# SCH_Cart_Main_PCB_2023-04-11.net
KiCad netlist of a schematic drawn in EasyEDA
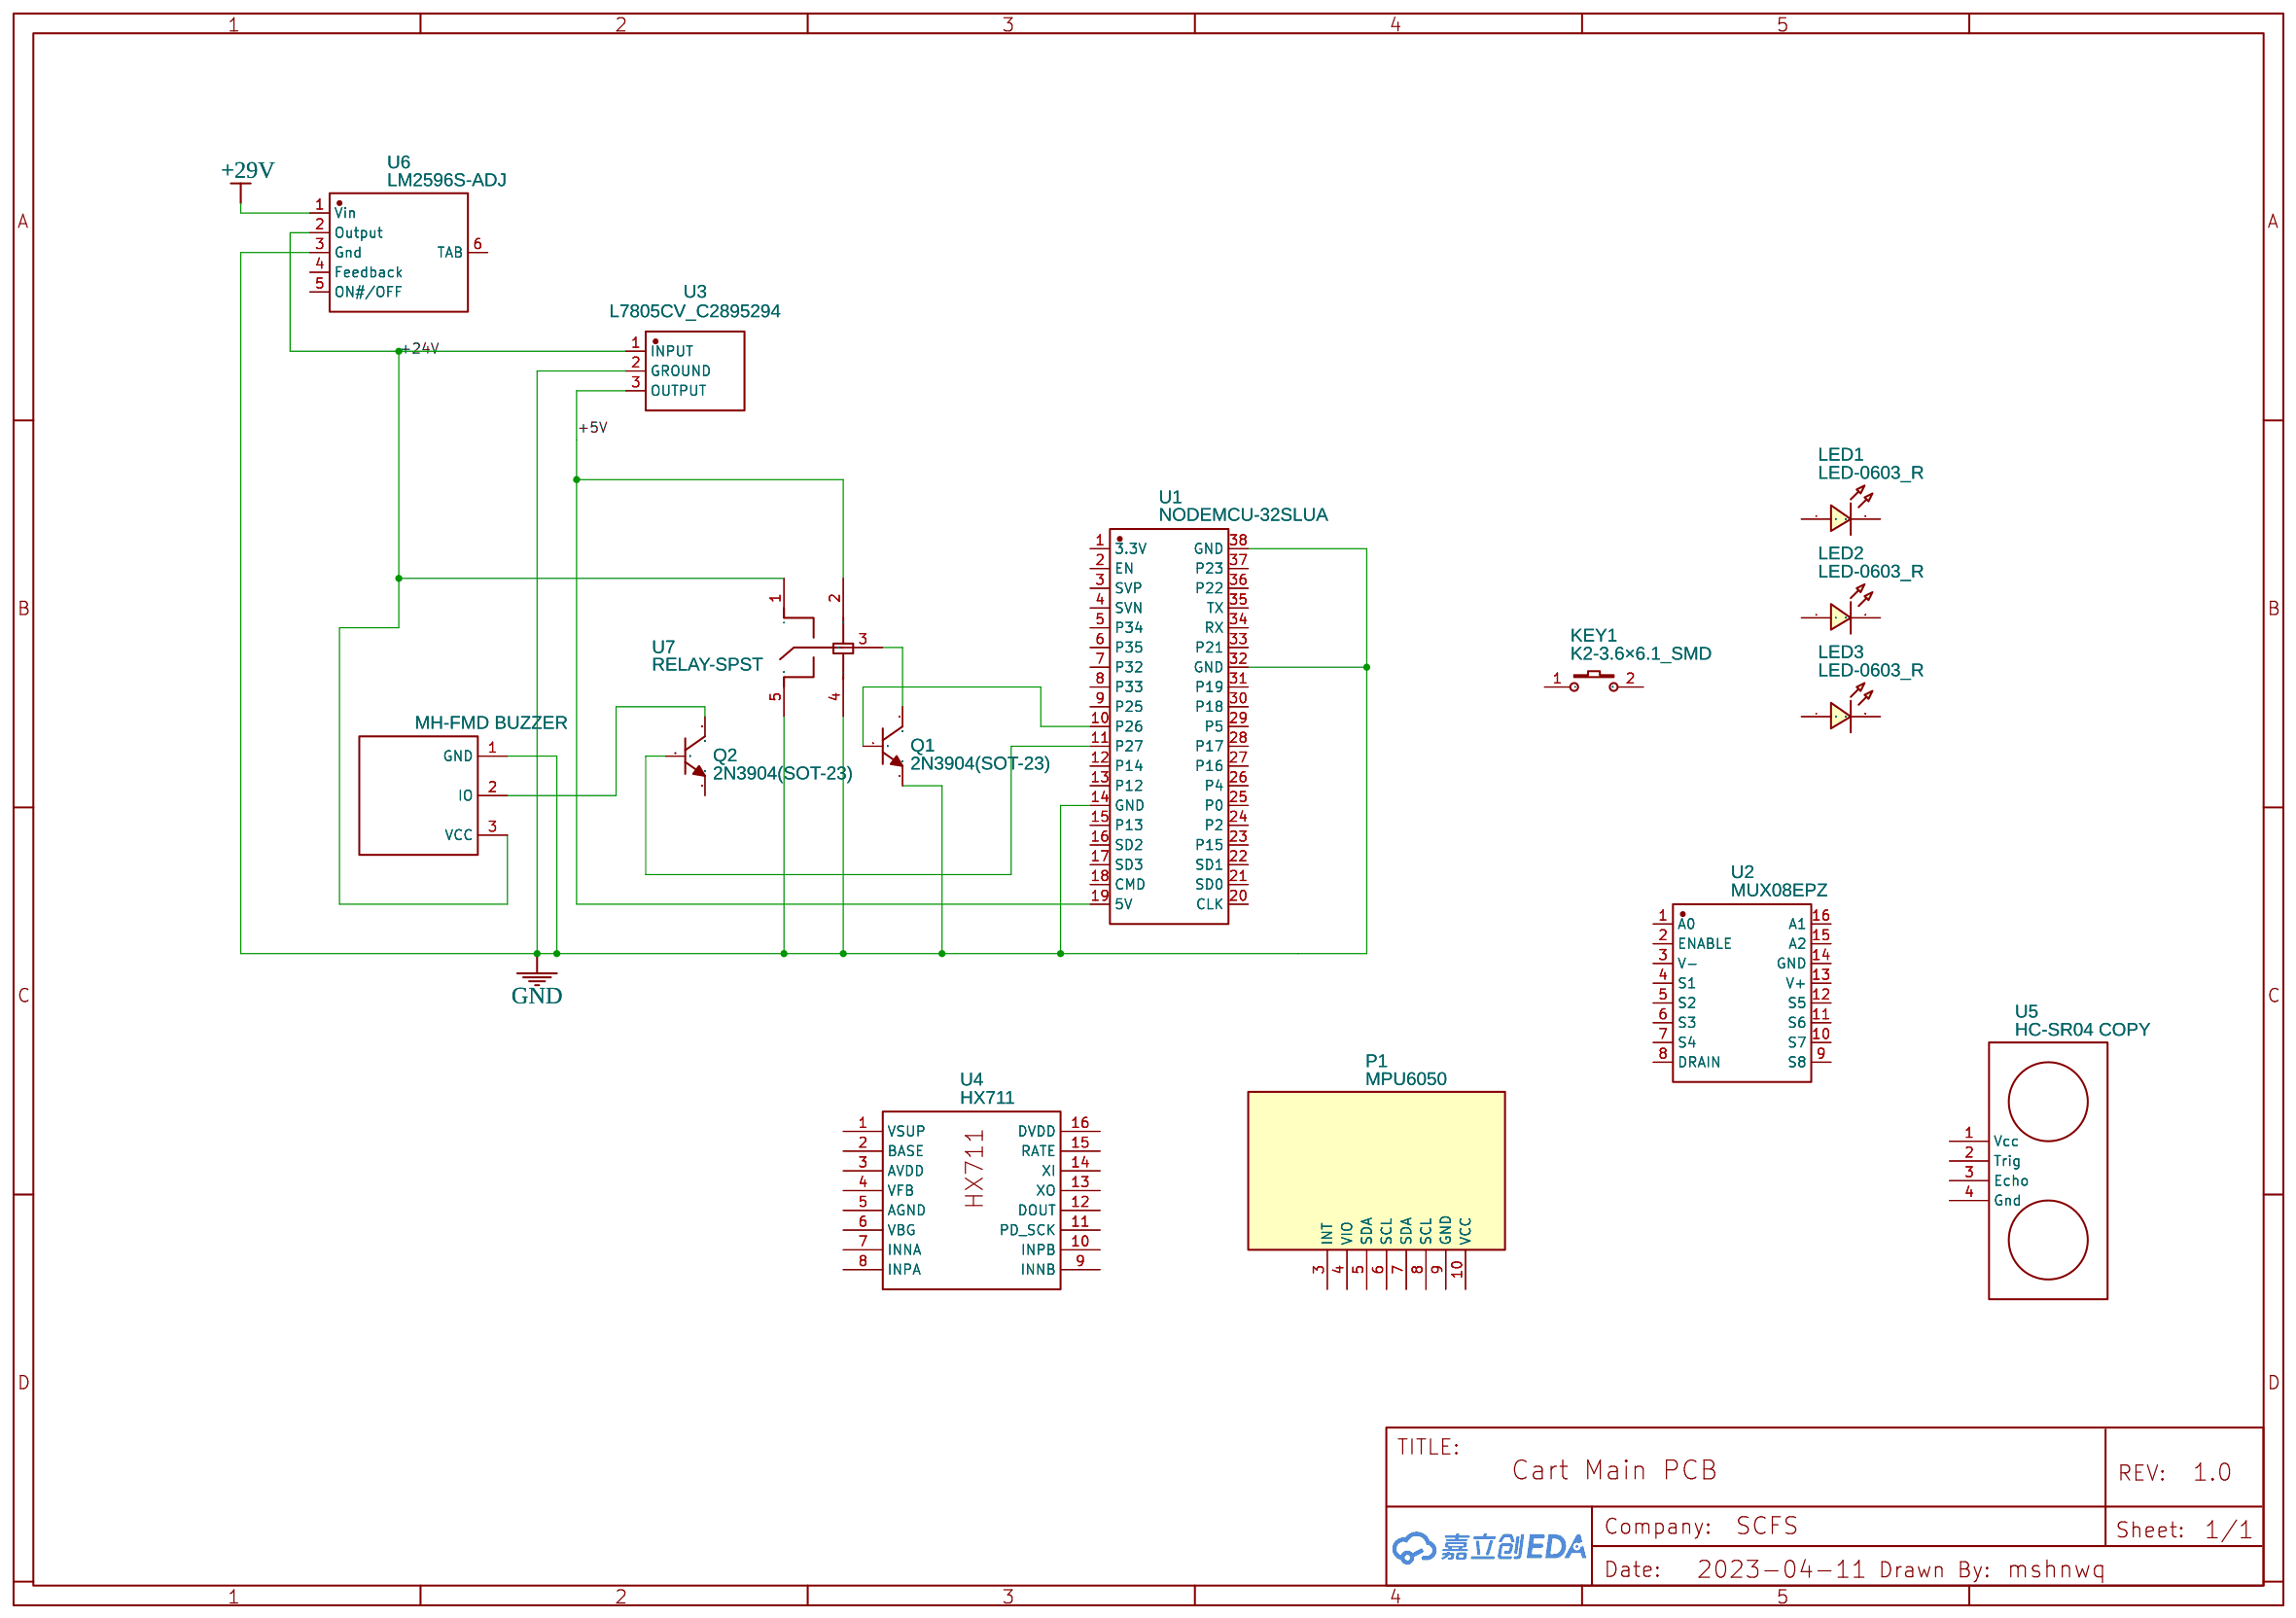
[diagram p0: schematic sheet]

(export (version "E")
  (design (tool "Eeschema 10.0.6"))
  (components
    (comp (ref "GND")
      (value "MH-FMD BUZZER")
      (fields (field (name "BOM_Supplier Part") "MH-FMD"))
      (libsource (lib "") (part "MH-FMD BUZZER"))
    )
    (comp (ref "KEY1")
      (value "K2-3.6×6.1_SMD")
      (fields
        (field (name "BOM_Manufacturer Part") "K2-1107ST-A4SW-06")
        (field (name "BOM_Supplier Part") "C118141")
      )
      (libsource (lib "") (part "K2-3.6×6.1_SMD"))
    )
    (comp (ref "LED1")
      (value "LED-0603_R")
      (fields
        (field (name "BOM_Manufacturer Part") "19-217/R6C-AL1M2VY/3T")
        (field (name "BOM_Supplier Part") "C72044")
      )
      (libsource (lib "") (part "LED-0603_R"))
    )
    (comp (ref "LED2")
      (value "LED-0603_R")
      (fields
        (field (name "BOM_Manufacturer Part") "19-217/R6C-AL1M2VY/3T")
        (field (name "BOM_Supplier Part") "C72044")
      )
      (libsource (lib "") (part "LED-0603_R"))
    )
    (comp (ref "LED3")
      (value "LED-0603_R")
      (fields
        (field (name "BOM_Manufacturer Part") "19-217/R6C-AL1M2VY/3T")
        (field (name "BOM_Supplier Part") "C72044")
      )
      (libsource (lib "") (part "LED-0603_R"))
    )
    (comp (ref "P1") (value "MPU6050") (libsource (lib "") (part "MPU6050")))
    (comp (ref "Q1")
      (value "2N3904(SOT-23)")
      (fields
        (field (name "BOM_Manufacturer Part") "2n3904S-RTK/PS")
        (field (name "BOM_Supplier Part") "C18536")
      )
      (libsource (lib "") (part "2N3904(SOT-23)"))
    )
    (comp (ref "Q2")
      (value "2N3904(SOT-23)")
      (fields
        (field (name "BOM_Manufacturer Part") "2n3904S-RTK/PS")
        (field (name "BOM_Supplier Part") "C18536")
      )
      (libsource (lib "") (part "2N3904(SOT-23)"))
    )
    (comp (ref "U1")
      (value "NODEMCU-32SLUA")
      (fields
        (field (name "BOM_Manufacturer Part") "NodeMCU-32SLua")
        (field (name "BOM_Supplier Part") "C111436")
      )
      (libsource (lib "") (part "NODEMCU-32SLUA"))
    )
    (comp (ref "U2")
      (value "MUX08EPZ")
      (fields (field (name "BOM_Supplier Part") "C690856"))
      (libsource (lib "") (part "MUX08EPZ"))
    )
    (comp (ref "U3")
      (value "L7805CV_C2895294")
      (fields
        (field (name "BOM_Manufacturer Part") "L7805CV带散热器")
        (field (name "BOM_Supplier Part") "C2895294")
      )
      (libsource (lib "") (part "L7805CV_C2895294"))
    )
    (comp (ref "U4")
      (value "HX711")
      (fields (field (name "BOM_Supplier Part") "C43656"))
      (libsource (lib "") (part "HX711"))
    )
    (comp (ref "U5") (value "HC-SR04 COPY") (libsource (lib "") (part "HC-SR04 COPY")))
    (comp (ref "U6")
      (value "LM2596S-ADJ")
      (fields (field (name "BOM_Supplier Part") "C347423"))
      (libsource (lib "") (part "LM2596S-ADJ"))
    )
    (comp (ref "U7")
      (value "RELAY-SPST")
      (fields
        (field (name "BOM_Manufacturer Part") "Relay-SPST")
        (field (name "BOM_Supplier Part") "C2941249")
      )
      (libsource (lib "") (part "RELAY-SPST"))
    )
  )
  (nets
    (net (code "1") (name "+29V") (class "Default")
      (node (ref "U6") (pin "1") (pinfunction "Vin_1") (pintype "unspecified"))
    )
    (net (code "2") (name "/+5V") (class "Default")
      (node (ref "U1") (pin "19") (pinfunction "5V_19") (pintype "unspecified"))
      (node (ref "U3") (pin "3") (pinfunction "OUTPUT_3") (pintype "unspecified"))
      (node (ref "U7") (pin "2") (pinfunction "2_2") (pintype "unspecified"))
    )
    (net (code "3") (name "/+24V") (class "Default")
      (node (ref "GND") (pin "3") (pinfunction "VCC_3") (pintype "unspecified"))
      (node (ref "U3") (pin "1") (pinfunction "INPUT_1") (pintype "unspecified"))
      (node (ref "U6") (pin "2") (pinfunction "Output_2") (pintype "unspecified"))
      (node (ref "U7") (pin "1") (pinfunction "1_1") (pintype "unspecified"))
    )
    (net (code "4") (name "GND") (class "Default")
      (node (ref "GND") (pin "1") (pinfunction "GND_1") (pintype "unspecified"))
      (node (ref "Q1") (pin "1") (pinfunction "E_1") (pintype "input"))
      (node (ref "U1") (pin "14") (pinfunction "GND_14") (pintype "unspecified"))
      (node (ref "U1") (pin "32") (pinfunction "GND_32") (pintype "unspecified"))
      (node (ref "U1") (pin "38") (pinfunction "GND_38") (pintype "unspecified"))
      (node (ref "U3") (pin "2") (pinfunction "GROUND_2") (pintype "unspecified"))
      (node (ref "U6") (pin "3") (pinfunction "Gnd_3") (pintype "unspecified"))
      (node (ref "U7") (pin "4") (pinfunction "4_4") (pintype "unspecified"))
      (node (ref "U7") (pin "5") (pinfunction "5_5") (pintype "unspecified"))
    )
    (net (code "5") (name "Net-(GND-IO)") (class "Default")
      (node (ref "GND") (pin "2") (pinfunction "IO_2") (pintype "unspecified"))
      (node (ref "Q2") (pin "3") (pinfunction "C_3") (pintype "input"))
    )
    (net (code "6") (name "Net-(Q1-B)") (class "Default")
      (node (ref "Q1") (pin "2") (pinfunction "B_2") (pintype "input"))
      (node (ref "U1") (pin "10") (pinfunction "P26_10") (pintype "unspecified"))
    )
    (net (code "7") (name "Net-(Q1-C)") (class "Default")
      (node (ref "Q1") (pin "3") (pinfunction "C_3") (pintype "input"))
      (node (ref "U7") (pin "3") (pinfunction "3_3") (pintype "unspecified"))
    )
    (net (code "8") (name "Net-(Q2-B)") (class "Default")
      (node (ref "Q2") (pin "2") (pinfunction "B_2") (pintype "input"))
      (node (ref "U1") (pin "11") (pinfunction "P27_11") (pintype "unspecified"))
    )
    (net (code "9") (name "unconnected-(KEY1-Pad1)") (class "Default")
      (node (ref "KEY1") (pin "1") (pinfunction "1_1") (pintype "unspecified"))
    )
    (net (code "10") (name "unconnected-(KEY1-Pad2)") (class "Default")
      (node (ref "KEY1") (pin "2") (pinfunction "2_2") (pintype "unspecified"))
    )
    (net (code "11") (name "unconnected-(LED1-Pad1)") (class "Default")
      (node (ref "LED1") (pin "1") (pinfunction "1_1") (pintype "unspecified"))
    )
    (net (code "12") (name "unconnected-(LED1-Pad2)") (class "Default")
      (node (ref "LED1") (pin "2") (pinfunction "2_2") (pintype "unspecified"))
    )
    (net (code "13") (name "unconnected-(LED2-Pad1)") (class "Default")
      (node (ref "LED2") (pin "1") (pinfunction "1_1") (pintype "unspecified"))
    )
    (net (code "14") (name "unconnected-(LED2-Pad2)") (class "Default")
      (node (ref "LED2") (pin "2") (pinfunction "2_2") (pintype "unspecified"))
    )
    (net (code "15") (name "unconnected-(LED3-Pad1)") (class "Default")
      (node (ref "LED3") (pin "1") (pinfunction "1_1") (pintype "unspecified"))
    )
    (net (code "16") (name "unconnected-(LED3-Pad2)") (class "Default")
      (node (ref "LED3") (pin "2") (pinfunction "2_2") (pintype "unspecified"))
    )
    (net (code "17") (name "unconnected-(P1-GND-Pad9)") (class "Default")
      (node (ref "P1") (pin "9") (pinfunction "GND_9") (pintype "unspecified"))
    )
    (net (code "18") (name "unconnected-(P1-INT-Pad3)") (class "Default")
      (node (ref "P1") (pin "3") (pinfunction "INT_3") (pintype "unspecified"))
    )
    (net (code "19") (name "unconnected-(P1-SCL-Pad6)") (class "Default")
      (node (ref "P1") (pin "6") (pinfunction "SCL_6") (pintype "unspecified"))
    )
    (net (code "20") (name "unconnected-(P1-SCL-Pad8)") (class "Default")
      (node (ref "P1") (pin "8") (pinfunction "SCL_8") (pintype "unspecified"))
    )
    (net (code "21") (name "unconnected-(P1-SDA-Pad5)") (class "Default")
      (node (ref "P1") (pin "5") (pinfunction "SDA_5") (pintype "unspecified"))
    )
    (net (code "22") (name "unconnected-(P1-SDA-Pad7)") (class "Default")
      (node (ref "P1") (pin "7") (pinfunction "SDA_7") (pintype "unspecified"))
    )
    (net (code "23") (name "unconnected-(P1-VCC-Pad10)") (class "Default")
      (node (ref "P1") (pin "10") (pinfunction "VCC_10") (pintype "unspecified"))
    )
    (net (code "24") (name "unconnected-(P1-VIO-Pad4)") (class "Default")
      (node (ref "P1") (pin "4") (pinfunction "VIO_4") (pintype "unspecified"))
    )
    (net (code "25") (name "unconnected-(Q2-E-Pad1)") (class "Default")
      (node (ref "Q2") (pin "1") (pinfunction "E_1") (pintype "input"))
    )
    (net (code "26") (name "unconnected-(U1-3.3V-Pad1)") (class "Default")
      (node (ref "U1") (pin "1") (pinfunction "3.3V_1") (pintype "unspecified"))
    )
    (net (code "27") (name "unconnected-(U1-CLK-Pad20)") (class "Default")
      (node (ref "U1") (pin "20") (pinfunction "CLK_20") (pintype "unspecified"))
    )
    (net (code "28") (name "unconnected-(U1-CMD-Pad18)") (class "Default")
      (node (ref "U1") (pin "18") (pinfunction "CMD_18") (pintype "unspecified"))
    )
    (net (code "29") (name "unconnected-(U1-EN-Pad2)") (class "Default")
      (node (ref "U1") (pin "2") (pinfunction "EN_2") (pintype "unspecified"))
    )
    (net (code "30") (name "unconnected-(U1-P0-Pad25)") (class "Default")
      (node (ref "U1") (pin "25") (pinfunction "P0_25") (pintype "unspecified"))
    )
    (net (code "31") (name "unconnected-(U1-P2-Pad24)") (class "Default")
      (node (ref "U1") (pin "24") (pinfunction "P2_24") (pintype "unspecified"))
    )
    (net (code "32") (name "unconnected-(U1-P4-Pad26)") (class "Default")
      (node (ref "U1") (pin "26") (pinfunction "P4_26") (pintype "unspecified"))
    )
    (net (code "33") (name "unconnected-(U1-P5-Pad29)") (class "Default")
      (node (ref "U1") (pin "29") (pinfunction "P5_29") (pintype "unspecified"))
    )
    (net (code "34") (name "unconnected-(U1-P12-Pad13)") (class "Default")
      (node (ref "U1") (pin "13") (pinfunction "P12_13") (pintype "unspecified"))
    )
    (net (code "35") (name "unconnected-(U1-P13-Pad15)") (class "Default")
      (node (ref "U1") (pin "15") (pinfunction "P13_15") (pintype "unspecified"))
    )
    (net (code "36") (name "unconnected-(U1-P14-Pad12)") (class "Default")
      (node (ref "U1") (pin "12") (pinfunction "P14_12") (pintype "unspecified"))
    )
    (net (code "37") (name "unconnected-(U1-P15-Pad23)") (class "Default")
      (node (ref "U1") (pin "23") (pinfunction "P15_23") (pintype "unspecified"))
    )
    (net (code "38") (name "unconnected-(U1-P16-Pad27)") (class "Default")
      (node (ref "U1") (pin "27") (pinfunction "P16_27") (pintype "unspecified"))
    )
    (net (code "39") (name "unconnected-(U1-P17-Pad28)") (class "Default")
      (node (ref "U1") (pin "28") (pinfunction "P17_28") (pintype "unspecified"))
    )
    (net (code "40") (name "unconnected-(U1-P18-Pad30)") (class "Default")
      (node (ref "U1") (pin "30") (pinfunction "P18_30") (pintype "unspecified"))
    )
    (net (code "41") (name "unconnected-(U1-P19-Pad31)") (class "Default")
      (node (ref "U1") (pin "31") (pinfunction "P19_31") (pintype "unspecified"))
    )
    (net (code "42") (name "unconnected-(U1-P21-Pad33)") (class "Default")
      (node (ref "U1") (pin "33") (pinfunction "P21_33") (pintype "unspecified"))
    )
    (net (code "43") (name "unconnected-(U1-P22-Pad36)") (class "Default")
      (node (ref "U1") (pin "36") (pinfunction "P22_36") (pintype "unspecified"))
    )
    (net (code "44") (name "unconnected-(U1-P23-Pad37)") (class "Default")
      (node (ref "U1") (pin "37") (pinfunction "P23_37") (pintype "unspecified"))
    )
    (net (code "45") (name "unconnected-(U1-P25-Pad9)") (class "Default")
      (node (ref "U1") (pin "9") (pinfunction "P25_9") (pintype "unspecified"))
    )
    (net (code "46") (name "unconnected-(U1-P32-Pad7)") (class "Default")
      (node (ref "U1") (pin "7") (pinfunction "P32_7") (pintype "unspecified"))
    )
    (net (code "47") (name "unconnected-(U1-P33-Pad8)") (class "Default")
      (node (ref "U1") (pin "8") (pinfunction "P33_8") (pintype "unspecified"))
    )
    (net (code "48") (name "unconnected-(U1-P34-Pad5)") (class "Default")
      (node (ref "U1") (pin "5") (pinfunction "P34_5") (pintype "unspecified"))
    )
    (net (code "49") (name "unconnected-(U1-P35-Pad6)") (class "Default")
      (node (ref "U1") (pin "6") (pinfunction "P35_6") (pintype "unspecified"))
    )
    (net (code "50") (name "unconnected-(U1-RX-Pad34)") (class "Default")
      (node (ref "U1") (pin "34") (pinfunction "RX_34") (pintype "unspecified"))
    )
    (net (code "51") (name "unconnected-(U1-SD0-Pad21)") (class "Default")
      (node (ref "U1") (pin "21") (pinfunction "SD0_21") (pintype "unspecified"))
    )
    (net (code "52") (name "unconnected-(U1-SD1-Pad22)") (class "Default")
      (node (ref "U1") (pin "22") (pinfunction "SD1_22") (pintype "unspecified"))
    )
    (net (code "53") (name "unconnected-(U1-SD2-Pad16)") (class "Default")
      (node (ref "U1") (pin "16") (pinfunction "SD2_16") (pintype "unspecified"))
    )
    (net (code "54") (name "unconnected-(U1-SD3-Pad17)") (class "Default")
      (node (ref "U1") (pin "17") (pinfunction "SD3_17") (pintype "unspecified"))
    )
    (net (code "55") (name "unconnected-(U1-SVN-Pad4)") (class "Default")
      (node (ref "U1") (pin "4") (pinfunction "SVN_4") (pintype "unspecified"))
    )
    (net (code "56") (name "unconnected-(U1-SVP-Pad3)") (class "Default")
      (node (ref "U1") (pin "3") (pinfunction "SVP_3") (pintype "unspecified"))
    )
    (net (code "57") (name "unconnected-(U1-TX-Pad35)") (class "Default")
      (node (ref "U1") (pin "35") (pinfunction "TX_35") (pintype "unspecified"))
    )
    (net (code "58") (name "unconnected-(U2-A0-Pad1)") (class "Default")
      (node (ref "U2") (pin "1") (pinfunction "A0_1") (pintype "unspecified"))
    )
    (net (code "59") (name "unconnected-(U2-A1-Pad16)") (class "Default")
      (node (ref "U2") (pin "16") (pinfunction "A1_16") (pintype "unspecified"))
    )
    (net (code "60") (name "unconnected-(U2-A2-Pad15)") (class "Default")
      (node (ref "U2") (pin "15") (pinfunction "A2_15") (pintype "unspecified"))
    )
    (net (code "61") (name "unconnected-(U2-DRAIN-Pad8)") (class "Default")
      (node (ref "U2") (pin "8") (pinfunction "DRAIN_8") (pintype "unspecified"))
    )
    (net (code "62") (name "unconnected-(U2-ENABLE-Pad2)") (class "Default")
      (node (ref "U2") (pin "2") (pinfunction "ENABLE_2") (pintype "unspecified"))
    )
    (net (code "63") (name "unconnected-(U2-GND-Pad14)") (class "Default")
      (node (ref "U2") (pin "14") (pinfunction "GND_14") (pintype "unspecified"))
    )
    (net (code "64") (name "unconnected-(U2-S1-Pad4)") (class "Default")
      (node (ref "U2") (pin "4") (pinfunction "S1_4") (pintype "unspecified"))
    )
    (net (code "65") (name "unconnected-(U2-S2-Pad5)") (class "Default")
      (node (ref "U2") (pin "5") (pinfunction "S2_5") (pintype "unspecified"))
    )
    (net (code "66") (name "unconnected-(U2-S3-Pad6)") (class "Default")
      (node (ref "U2") (pin "6") (pinfunction "S3_6") (pintype "unspecified"))
    )
    (net (code "67") (name "unconnected-(U2-S4-Pad7)") (class "Default")
      (node (ref "U2") (pin "7") (pinfunction "S4_7") (pintype "unspecified"))
    )
    (net (code "68") (name "unconnected-(U2-S5-Pad12)") (class "Default")
      (node (ref "U2") (pin "12") (pinfunction "S5_12") (pintype "unspecified"))
    )
    (net (code "69") (name "unconnected-(U2-S6-Pad11)") (class "Default")
      (node (ref "U2") (pin "11") (pinfunction "S6_11") (pintype "unspecified"))
    )
    (net (code "70") (name "unconnected-(U2-S7-Pad10)") (class "Default")
      (node (ref "U2") (pin "10") (pinfunction "S7_10") (pintype "unspecified"))
    )
    (net (code "71") (name "unconnected-(U2-S8-Pad9)") (class "Default")
      (node (ref "U2") (pin "9") (pinfunction "S8_9") (pintype "unspecified"))
    )
    (net (code "72") (name "unconnected-(U2-V+-Pad13)") (class "Default")
      (node (ref "U2") (pin "13") (pinfunction "V+_13") (pintype "unspecified"))
    )
    (net (code "73") (name "unconnected-(U2-V--Pad3)") (class "Default")
      (node (ref "U2") (pin "3") (pinfunction "V-_3") (pintype "unspecified"))
    )
    (net (code "74") (name "unconnected-(U4-AGND-Pad5)") (class "Default")
      (node (ref "U4") (pin "5") (pinfunction "AGND_5") (pintype "unspecified"))
    )
    (net (code "75") (name "unconnected-(U4-AVDD-Pad3)") (class "Default")
      (node (ref "U4") (pin "3") (pinfunction "AVDD_3") (pintype "unspecified"))
    )
    (net (code "76") (name "unconnected-(U4-BASE-Pad2)") (class "Default")
      (node (ref "U4") (pin "2") (pinfunction "BASE_2") (pintype "unspecified"))
    )
    (net (code "77") (name "unconnected-(U4-DOUT-Pad12)") (class "Default")
      (node (ref "U4") (pin "12") (pinfunction "DOUT_12") (pintype "unspecified"))
    )
    (net (code "78") (name "unconnected-(U4-DVDD-Pad16)") (class "Default")
      (node (ref "U4") (pin "16") (pinfunction "DVDD_16") (pintype "unspecified"))
    )
    (net (code "79") (name "unconnected-(U4-INNA-Pad7)") (class "Default")
      (node (ref "U4") (pin "7") (pinfunction "INNA_7") (pintype "unspecified"))
    )
    (net (code "80") (name "unconnected-(U4-INNB-Pad9)") (class "Default")
      (node (ref "U4") (pin "9") (pinfunction "INNB_9") (pintype "unspecified"))
    )
    (net (code "81") (name "unconnected-(U4-INPA-Pad8)") (class "Default")
      (node (ref "U4") (pin "8") (pinfunction "INPA_8") (pintype "unspecified"))
    )
    (net (code "82") (name "unconnected-(U4-INPB-Pad10)") (class "Default")
      (node (ref "U4") (pin "10") (pinfunction "INPB_10") (pintype "unspecified"))
    )
    (net (code "83") (name "unconnected-(U4-PD_SCK-Pad11)") (class "Default")
      (node (ref "U4") (pin "11") (pinfunction "PD_SCK_11") (pintype "unspecified"))
    )
    (net (code "84") (name "unconnected-(U4-RATE-Pad15)") (class "Default")
      (node (ref "U4") (pin "15") (pinfunction "RATE_15") (pintype "unspecified"))
    )
    (net (code "85") (name "unconnected-(U4-VBG-Pad6)") (class "Default")
      (node (ref "U4") (pin "6") (pinfunction "VBG_6") (pintype "unspecified"))
    )
    (net (code "86") (name "unconnected-(U4-VFB-Pad4)") (class "Default")
      (node (ref "U4") (pin "4") (pinfunction "VFB_4") (pintype "unspecified"))
    )
    (net (code "87") (name "unconnected-(U4-VSUP-Pad1)") (class "Default")
      (node (ref "U4") (pin "1") (pinfunction "VSUP_1") (pintype "unspecified"))
    )
    (net (code "88") (name "unconnected-(U4-XI-Pad14)") (class "Default")
      (node (ref "U4") (pin "14") (pinfunction "XI_14") (pintype "unspecified"))
    )
    (net (code "89") (name "unconnected-(U4-XO-Pad13)") (class "Default")
      (node (ref "U4") (pin "13") (pinfunction "XO_13") (pintype "unspecified"))
    )
    (net (code "90") (name "unconnected-(U5-Echo-Pad3)") (class "Default")
      (node (ref "U5") (pin "3") (pinfunction "Echo_3") (pintype "unspecified"))
    )
    (net (code "91") (name "unconnected-(U5-Gnd-Pad4)") (class "Default")
      (node (ref "U5") (pin "4") (pinfunction "Gnd_4") (pintype "unspecified"))
    )
    (net (code "92") (name "unconnected-(U5-Trig-Pad2)") (class "Default")
      (node (ref "U5") (pin "2") (pinfunction "Trig_2") (pintype "unspecified"))
    )
    (net (code "93") (name "unconnected-(U5-Vcc-Pad1)") (class "Default")
      (node (ref "U5") (pin "1") (pinfunction "Vcc_1") (pintype "unspecified"))
    )
    (net (code "94") (name "unconnected-(U6-Feedback-Pad4)") (class "Default")
      (node (ref "U6") (pin "4") (pinfunction "Feedback_4") (pintype "unspecified"))
    )
    (net (code "95") (name "unconnected-(U6-ON#{slash}OFF-Pad5)") (class "Default")
      (node (ref "U6") (pin "5") (pinfunction "ON#/OFF_5") (pintype "unspecified"))
    )
    (net (code "96") (name "unconnected-(U6-TAB-Pad6)") (class "Default")
      (node (ref "U6") (pin "6") (pinfunction "TAB_6") (pintype "unspecified"))
    )
  )
)
